# Apollon_TLM_testing.net
KiCad netlist of a schematic drawn in EasyEDA
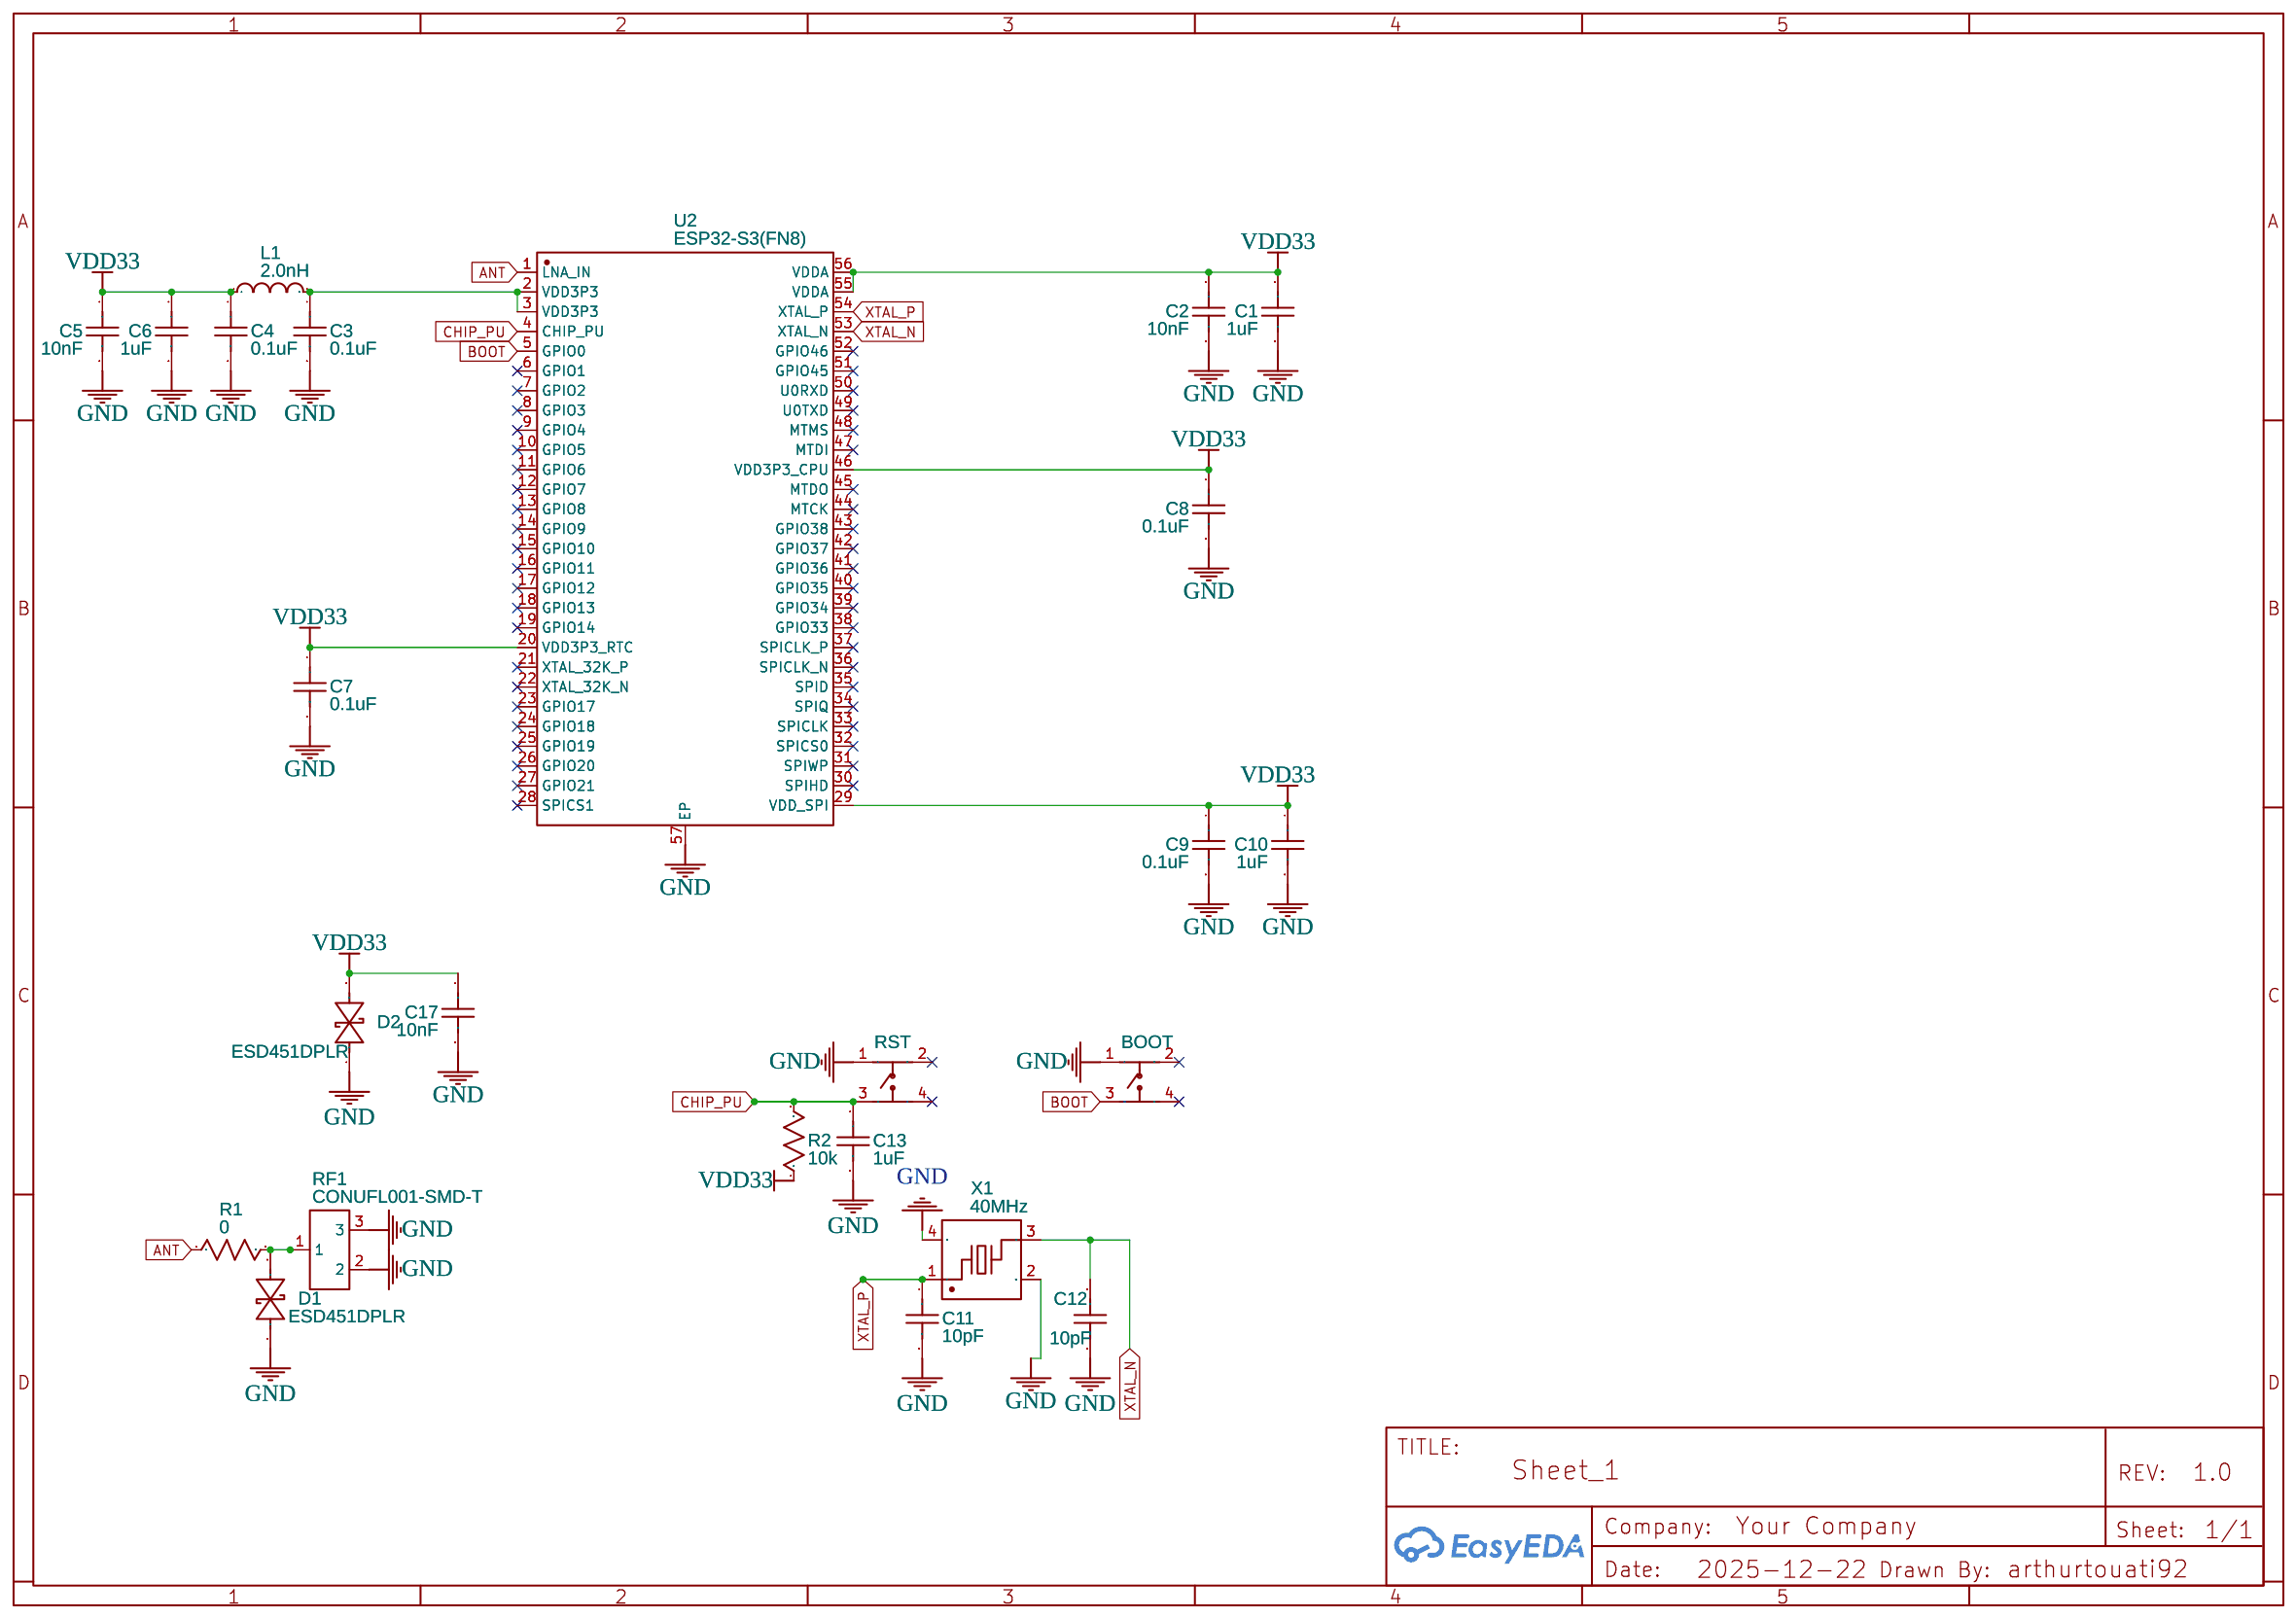
[diagram p0: schematic sheet]

(export (version "E")
  (design (tool "Eeschema 10.0.6"))
  (components
    (comp (ref "BOOT")
      (value "C4B1802110")
      (fields (field (name "Manufacturer") "SAMZO(三佐)"))
      (libsource (lib "") (part "C4B1802110_1"))
    )
    (comp (ref "C1") (value "1uF") (libsource (lib "") (part "C_0402_US")))
    (comp (ref "C2") (value "10nF") (libsource (lib "") (part "C_0402_US")))
    (comp (ref "C3") (value "0.1uF") (libsource (lib "") (part "C_0402_US_1")))
    (comp (ref "C4") (value "0.1uF") (libsource (lib "") (part "C_0402_US_1")))
    (comp (ref "C5") (value "10nF") (libsource (lib "") (part "C_0402_US")))
    (comp (ref "C6") (value "1uF") (libsource (lib "") (part "C_0402_US")))
    (comp (ref "C7") (value "0.1uF") (libsource (lib "") (part "C_0402_US_1")))
    (comp (ref "C8") (value "0.1uF") (libsource (lib "") (part "C_0402_US")))
    (comp (ref "C9") (value "0.1uF") (libsource (lib "") (part "C_0402_US")))
    (comp (ref "C10") (value "1uF") (libsource (lib "") (part "C_0402_US")))
    (comp (ref "C11") (value "10pF") (libsource (lib "") (part "C_0402_US_1")))
    (comp (ref "C12") (value "10pF") (libsource (lib "") (part "C_0402_US_1")))
    (comp (ref "C13") (value "1uF") (libsource (lib "") (part "C_0402_US_1")))
    (comp (ref "C17") (value "10nF") (libsource (lib "") (part "C_0402_US")))
    (comp (ref "D1")
      (value "ESD451DPLR")
      (fields (field (name "Manufacturer") "TI(德州仪器)"))
      (libsource (lib "") (part "ESD451DPLR"))
    )
    (comp (ref "D2")
      (value "ESD451DPLR")
      (fields (field (name "Manufacturer") "TI(德州仪器)"))
      (libsource (lib "") (part "ESD451DPLR"))
    )
    (comp (ref "L1") (value "2.0nH") (libsource (lib "") (part "L0402_US")))
    (comp (ref "R1") (value "0") (libsource (lib "") (part "R_0402_US")))
    (comp (ref "R2") (value "10k") (libsource (lib "") (part "R_0402_US_1")))
    (comp (ref "RF1")
      (value "CONUFL001-SMD-T")
      (fields (field (name "Manufacturer") "TE Connectivity(泰科电子)"))
      (libsource (lib "") (part "CONUFL001-SMD-T"))
    )
    (comp (ref "RST")
      (value "C4B1802110")
      (fields (field (name "Manufacturer") "SAMZO(三佐)"))
      (libsource (lib "") (part "C4B1802110"))
    )
    (comp (ref "U2")
      (value "ESP32-S3(FN8)")
      (fields (field (name "Manufacturer Part") "ESP32-S3FN8") (field (name "Manufacturer") "ESPRESSIF(乐鑫)"))
      (libsource (lib "") (part "ESP32-S3(FN8)"))
    )
    (comp (ref "X1")
      (value "40MHz")
      (fields
        (field (name "Manufacturer Part") "XL2EL89CPI-111YLC-40M")
        (field (name "Manufacturer") "YXC(扬兴晶振)")
      )
      (libsource (lib "") (part "XL2EL89CPI-111YLC-40M"))
    )
  )
  (nets
    (net (code "1") (name "ANT") (class "Default")
      (node (ref "R1") (pin "1") (pinfunction "1_1") (pintype "unspecified"))
      (node (ref "U2") (pin "1") (pinfunction "LNA_IN_1") (pintype "unspecified"))
    )
    (net (code "2") (name "BOOT") (class "Default")
      (node (ref "BOOT") (pin "3") (pinfunction "3_3") (pintype "unspecified"))
      (node (ref "U2") (pin "5") (pinfunction "GPIO0_5") (pintype "unspecified"))
    )
    (net (code "3") (name "CHIP_PU") (class "Default")
      (node (ref "C13") (pin "1") (pinfunction "1_1") (pintype "unspecified"))
      (node (ref "R2") (pin "2") (pinfunction "2_2") (pintype "unspecified"))
      (node (ref "RST") (pin "3") (pinfunction "3_3") (pintype "unspecified"))
      (node (ref "U2") (pin "4") (pinfunction "CHIP_PU_4") (pintype "unspecified"))
    )
    (net (code "4") (name "GND") (class "Default")
      (node (ref "BOOT") (pin "1") (pinfunction "1_1") (pintype "unspecified"))
      (node (ref "C1") (pin "2") (pinfunction "2_2") (pintype "unspecified"))
      (node (ref "C10") (pin "2") (pinfunction "2_2") (pintype "unspecified"))
      (node (ref "C11") (pin "2") (pinfunction "2_2") (pintype "unspecified"))
      (node (ref "C12") (pin "2") (pinfunction "2_2") (pintype "unspecified"))
      (node (ref "C13") (pin "2") (pinfunction "2_2") (pintype "unspecified"))
      (node (ref "C17") (pin "2") (pinfunction "2_2") (pintype "unspecified"))
      (node (ref "C2") (pin "2") (pinfunction "2_2") (pintype "unspecified"))
      (node (ref "C3") (pin "2") (pinfunction "2_2") (pintype "unspecified"))
      (node (ref "C4") (pin "2") (pinfunction "2_2") (pintype "unspecified"))
      (node (ref "C5") (pin "2") (pinfunction "2_2") (pintype "unspecified"))
      (node (ref "C6") (pin "2") (pinfunction "2_2") (pintype "unspecified"))
      (node (ref "C7") (pin "2") (pinfunction "2_2") (pintype "unspecified"))
      (node (ref "C8") (pin "2") (pinfunction "2_2") (pintype "unspecified"))
      (node (ref "C9") (pin "2") (pinfunction "2_2") (pintype "unspecified"))
      (node (ref "D1") (pin "1") (pinfunction "1_1") (pintype "unspecified"))
      (node (ref "D2") (pin "1") (pinfunction "1_1") (pintype "unspecified"))
      (node (ref "RF1") (pin "2") (pinfunction "2_2") (pintype "unspecified"))
      (node (ref "RF1") (pin "3") (pinfunction "3_3") (pintype "unspecified"))
      (node (ref "RST") (pin "1") (pinfunction "1_1") (pintype "unspecified"))
      (node (ref "U2") (pin "57") (pinfunction "EP_57") (pintype "unspecified"))
      (node (ref "X1") (pin "2") (pinfunction "GND_2") (pintype "input"))
      (node (ref "X1") (pin "4") (pinfunction "GND_4") (pintype "input"))
    )
    (net (code "5") (name "Net-(C3-Pad1)") (class "Default")
      (node (ref "C3") (pin "1") (pinfunction "1_1") (pintype "unspecified"))
      (node (ref "L1") (pin "2") (pinfunction "2_2") (pintype "unspecified"))
      (node (ref "U2") (pin "2") (pinfunction "VDD3P3_2") (pintype "unspecified"))
      (node (ref "U2") (pin "3") (pinfunction "VDD3P3_3") (pintype "unspecified"))
    )
    (net (code "6") (name "Net-(D1-Pad2)") (class "Default")
      (node (ref "D1") (pin "2") (pinfunction "2_2") (pintype "unspecified"))
      (node (ref "R1") (pin "2") (pinfunction "2_2") (pintype "unspecified"))
      (node (ref "RF1") (pin "1") (pinfunction "1_1") (pintype "unspecified"))
    )
    (net (code "7") (name "VDD33") (class "Default")
      (node (ref "C1") (pin "1") (pinfunction "1_1") (pintype "unspecified"))
      (node (ref "C10") (pin "1") (pinfunction "1_1") (pintype "unspecified"))
      (node (ref "C17") (pin "1") (pinfunction "1_1") (pintype "unspecified"))
      (node (ref "C2") (pin "1") (pinfunction "1_1") (pintype "unspecified"))
      (node (ref "C4") (pin "1") (pinfunction "1_1") (pintype "unspecified"))
      (node (ref "C5") (pin "1") (pinfunction "1_1") (pintype "unspecified"))
      (node (ref "C6") (pin "1") (pinfunction "1_1") (pintype "unspecified"))
      (node (ref "C7") (pin "1") (pinfunction "1_1") (pintype "unspecified"))
      (node (ref "C8") (pin "1") (pinfunction "1_1") (pintype "unspecified"))
      (node (ref "C9") (pin "1") (pinfunction "1_1") (pintype "unspecified"))
      (node (ref "D2") (pin "2") (pinfunction "2_2") (pintype "unspecified"))
      (node (ref "L1") (pin "1") (pinfunction "1_1") (pintype "unspecified"))
      (node (ref "R2") (pin "1") (pinfunction "1_1") (pintype "unspecified"))
      (node (ref "U2") (pin "20") (pinfunction "VDD3P3_RTC_20") (pintype "unspecified"))
      (node (ref "U2") (pin "29") (pinfunction "VDD_SPI_29") (pintype "unspecified"))
      (node (ref "U2") (pin "46") (pinfunction "VDD3P3_CPU_46") (pintype "unspecified"))
      (node (ref "U2") (pin "55") (pinfunction "VDDA_55") (pintype "unspecified"))
      (node (ref "U2") (pin "56") (pinfunction "VDDA_56") (pintype "unspecified"))
    )
    (net (code "8") (name "XTAL_N") (class "Default")
      (node (ref "C12") (pin "1") (pinfunction "1_1") (pintype "unspecified"))
      (node (ref "U2") (pin "53") (pinfunction "XTAL_N_53") (pintype "unspecified"))
      (node (ref "X1") (pin "3") (pinfunction "3_3") (pintype "input"))
    )
    (net (code "9") (name "XTAL_P") (class "Default")
      (node (ref "C11") (pin "1") (pinfunction "1_1") (pintype "unspecified"))
      (node (ref "U2") (pin "54") (pinfunction "XTAL_P_54") (pintype "unspecified"))
      (node (ref "X1") (pin "1") (pinfunction "1_1") (pintype "input"))
    )
    (net (code "10") (name "unconnected-(BOOT-Pad2)") (class "Default")
      (node (ref "BOOT") (pin "2") (pinfunction "2_2") (pintype "unspecified+no_connect"))
    )
    (net (code "11") (name "unconnected-(BOOT-Pad4)") (class "Default")
      (node (ref "BOOT") (pin "4") (pinfunction "4_4") (pintype "unspecified+no_connect"))
    )
    (net (code "12") (name "unconnected-(RST-Pad2)") (class "Default")
      (node (ref "RST") (pin "2") (pinfunction "2_2") (pintype "unspecified+no_connect"))
    )
    (net (code "13") (name "unconnected-(RST-Pad4)") (class "Default")
      (node (ref "RST") (pin "4") (pinfunction "4_4") (pintype "unspecified+no_connect"))
    )
    (net (code "14") (name "unconnected-(U2-GPIO1-Pad6)") (class "Default")
      (node (ref "U2") (pin "6") (pinfunction "GPIO1_6") (pintype "unspecified+no_connect"))
    )
    (net (code "15") (name "unconnected-(U2-GPIO2-Pad7)") (class "Default")
      (node (ref "U2") (pin "7") (pinfunction "GPIO2_7") (pintype "unspecified+no_connect"))
    )
    (net (code "16") (name "unconnected-(U2-GPIO3-Pad8)") (class "Default")
      (node (ref "U2") (pin "8") (pinfunction "GPIO3_8") (pintype "unspecified+no_connect"))
    )
    (net (code "17") (name "unconnected-(U2-GPIO4-Pad9)") (class "Default")
      (node (ref "U2") (pin "9") (pinfunction "GPIO4_9") (pintype "unspecified+no_connect"))
    )
    (net (code "18") (name "unconnected-(U2-GPIO5-Pad10)") (class "Default")
      (node (ref "U2") (pin "10") (pinfunction "GPIO5_10") (pintype "unspecified+no_connect"))
    )
    (net (code "19") (name "unconnected-(U2-GPIO6-Pad11)") (class "Default")
      (node (ref "U2") (pin "11") (pinfunction "GPIO6_11") (pintype "unspecified+no_connect"))
    )
    (net (code "20") (name "unconnected-(U2-GPIO7-Pad12)") (class "Default")
      (node (ref "U2") (pin "12") (pinfunction "GPIO7_12") (pintype "unspecified+no_connect"))
    )
    (net (code "21") (name "unconnected-(U2-GPIO8-Pad13)") (class "Default")
      (node (ref "U2") (pin "13") (pinfunction "GPIO8_13") (pintype "unspecified+no_connect"))
    )
    (net (code "22") (name "unconnected-(U2-GPIO9-Pad14)") (class "Default")
      (node (ref "U2") (pin "14") (pinfunction "GPIO9_14") (pintype "unspecified+no_connect"))
    )
    (net (code "23") (name "unconnected-(U2-GPIO10-Pad15)") (class "Default")
      (node (ref "U2") (pin "15") (pinfunction "GPIO10_15") (pintype "unspecified+no_connect"))
    )
    (net (code "24") (name "unconnected-(U2-GPIO11-Pad16)") (class "Default")
      (node (ref "U2") (pin "16") (pinfunction "GPIO11_16") (pintype "unspecified+no_connect"))
    )
    (net (code "25") (name "unconnected-(U2-GPIO12-Pad17)") (class "Default")
      (node (ref "U2") (pin "17") (pinfunction "GPIO12_17") (pintype "unspecified+no_connect"))
    )
    (net (code "26") (name "unconnected-(U2-GPIO13-Pad18)") (class "Default")
      (node (ref "U2") (pin "18") (pinfunction "GPIO13_18") (pintype "unspecified+no_connect"))
    )
    (net (code "27") (name "unconnected-(U2-GPIO14-Pad19)") (class "Default")
      (node (ref "U2") (pin "19") (pinfunction "GPIO14_19") (pintype "unspecified+no_connect"))
    )
    (net (code "28") (name "unconnected-(U2-GPIO17-Pad23)") (class "Default")
      (node (ref "U2") (pin "23") (pinfunction "GPIO17_23") (pintype "unspecified+no_connect"))
    )
    (net (code "29") (name "unconnected-(U2-GPIO18-Pad24)") (class "Default")
      (node (ref "U2") (pin "24") (pinfunction "GPIO18_24") (pintype "unspecified+no_connect"))
    )
    (net (code "30") (name "unconnected-(U2-GPIO19-Pad25)") (class "Default")
      (node (ref "U2") (pin "25") (pinfunction "GPIO19_25") (pintype "unspecified+no_connect"))
    )
    (net (code "31") (name "unconnected-(U2-GPIO20-Pad26)") (class "Default")
      (node (ref "U2") (pin "26") (pinfunction "GPIO20_26") (pintype "unspecified+no_connect"))
    )
    (net (code "32") (name "unconnected-(U2-GPIO21-Pad27)") (class "Default")
      (node (ref "U2") (pin "27") (pinfunction "GPIO21_27") (pintype "unspecified+no_connect"))
    )
    (net (code "33") (name "unconnected-(U2-GPIO33-Pad38)") (class "Default")
      (node (ref "U2") (pin "38") (pinfunction "GPIO33_38") (pintype "unspecified+no_connect"))
    )
    (net (code "34") (name "unconnected-(U2-GPIO34-Pad39)") (class "Default")
      (node (ref "U2") (pin "39") (pinfunction "GPIO34_39") (pintype "unspecified+no_connect"))
    )
    (net (code "35") (name "unconnected-(U2-GPIO35-Pad40)") (class "Default")
      (node (ref "U2") (pin "40") (pinfunction "GPIO35_40") (pintype "unspecified+no_connect"))
    )
    (net (code "36") (name "unconnected-(U2-GPIO36-Pad41)") (class "Default")
      (node (ref "U2") (pin "41") (pinfunction "GPIO36_41") (pintype "unspecified+no_connect"))
    )
    (net (code "37") (name "unconnected-(U2-GPIO37-Pad42)") (class "Default")
      (node (ref "U2") (pin "42") (pinfunction "GPIO37_42") (pintype "unspecified+no_connect"))
    )
    (net (code "38") (name "unconnected-(U2-GPIO38-Pad43)") (class "Default")
      (node (ref "U2") (pin "43") (pinfunction "GPIO38_43") (pintype "unspecified+no_connect"))
    )
    (net (code "39") (name "unconnected-(U2-GPIO45-Pad51)") (class "Default")
      (node (ref "U2") (pin "51") (pinfunction "GPIO45_51") (pintype "unspecified+no_connect"))
    )
    (net (code "40") (name "unconnected-(U2-GPIO46-Pad52)") (class "Default")
      (node (ref "U2") (pin "52") (pinfunction "GPIO46_52") (pintype "unspecified+no_connect"))
    )
    (net (code "41") (name "unconnected-(U2-MTCK-Pad44)") (class "Default")
      (node (ref "U2") (pin "44") (pinfunction "MTCK_44") (pintype "unspecified+no_connect"))
    )
    (net (code "42") (name "unconnected-(U2-MTDI-Pad47)") (class "Default")
      (node (ref "U2") (pin "47") (pinfunction "MTDI_47") (pintype "unspecified+no_connect"))
    )
    (net (code "43") (name "unconnected-(U2-MTDO-Pad45)") (class "Default")
      (node (ref "U2") (pin "45") (pinfunction "MTDO_45") (pintype "unspecified+no_connect"))
    )
    (net (code "44") (name "unconnected-(U2-MTMS-Pad48)") (class "Default")
      (node (ref "U2") (pin "48") (pinfunction "MTMS_48") (pintype "unspecified+no_connect"))
    )
    (net (code "45") (name "unconnected-(U2-SPICLK-Pad33)") (class "Default")
      (node (ref "U2") (pin "33") (pinfunction "SPICLK_33") (pintype "unspecified+no_connect"))
    )
    (net (code "46") (name "unconnected-(U2-SPICLK_N-Pad36)") (class "Default")
      (node (ref "U2") (pin "36") (pinfunction "SPICLK_N_36") (pintype "unspecified+no_connect"))
    )
    (net (code "47") (name "unconnected-(U2-SPICLK_P-Pad37)") (class "Default")
      (node (ref "U2") (pin "37") (pinfunction "SPICLK_P_37") (pintype "unspecified+no_connect"))
    )
    (net (code "48") (name "unconnected-(U2-SPICS0-Pad32)") (class "Default")
      (node (ref "U2") (pin "32") (pinfunction "SPICS0_32") (pintype "unspecified+no_connect"))
    )
    (net (code "49") (name "unconnected-(U2-SPICS1-Pad28)") (class "Default")
      (node (ref "U2") (pin "28") (pinfunction "SPICS1_28") (pintype "unspecified+no_connect"))
    )
    (net (code "50") (name "unconnected-(U2-SPID-Pad35)") (class "Default")
      (node (ref "U2") (pin "35") (pinfunction "SPID_35") (pintype "unspecified+no_connect"))
    )
    (net (code "51") (name "unconnected-(U2-SPIHD-Pad30)") (class "Default")
      (node (ref "U2") (pin "30") (pinfunction "SPIHD_30") (pintype "unspecified+no_connect"))
    )
    (net (code "52") (name "unconnected-(U2-SPIQ-Pad34)") (class "Default")
      (node (ref "U2") (pin "34") (pinfunction "SPIQ_34") (pintype "unspecified+no_connect"))
    )
    (net (code "53") (name "unconnected-(U2-SPIWP-Pad31)") (class "Default")
      (node (ref "U2") (pin "31") (pinfunction "SPIWP_31") (pintype "unspecified+no_connect"))
    )
    (net (code "54") (name "unconnected-(U2-U0RXD-Pad50)") (class "Default")
      (node (ref "U2") (pin "50") (pinfunction "U0RXD_50") (pintype "unspecified+no_connect"))
    )
    (net (code "55") (name "unconnected-(U2-U0TXD-Pad49)") (class "Default")
      (node (ref "U2") (pin "49") (pinfunction "U0TXD_49") (pintype "unspecified+no_connect"))
    )
    (net (code "56") (name "unconnected-(U2-XTAL_32K_N-Pad22)") (class "Default")
      (node (ref "U2") (pin "22") (pinfunction "XTAL_32K_N_22") (pintype "unspecified+no_connect"))
    )
    (net (code "57") (name "unconnected-(U2-XTAL_32K_P-Pad21)") (class "Default")
      (node (ref "U2") (pin "21") (pinfunction "XTAL_32K_P_21") (pintype "unspecified+no_connect"))
    )
  )
)
